# -46342_21-004_3_4.net
KiCad netlist of a schematic drawn in Altium Designer
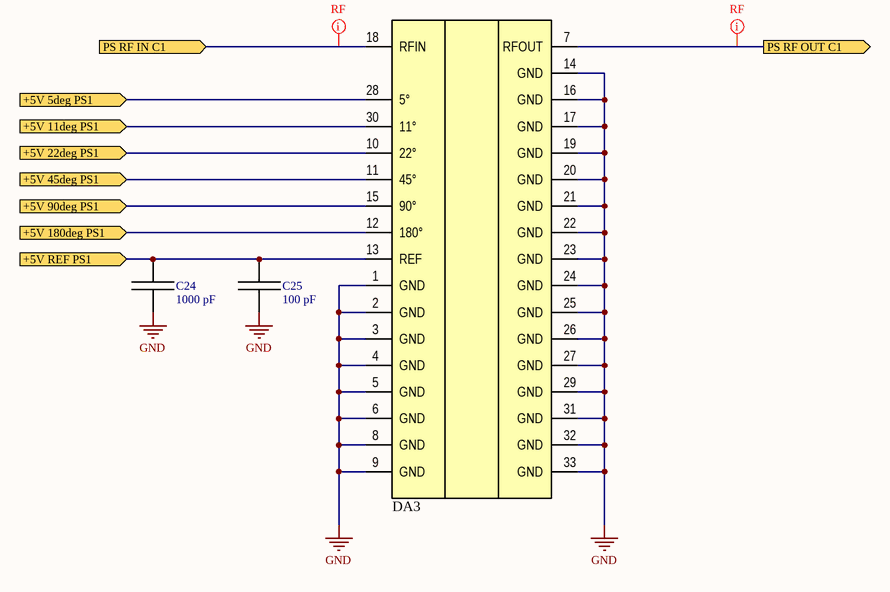
[diagram p0: МПСУ-46342.21-004 Э3 Лист4.SchDoc]

(export (version "E")
  (design (tool "Eeschema 10.0.6"))
  (components
    (comp (ref "C24")
      (value "1000 pF")
      (footprint "CAPC100X50X55L20N")
      (description "Capacitor, generic")
      (fields (field (name "TOLERANCE") "5 %"))
      (libsource (lib "StudentsLibrary") (part "Capacitor"))
    )
    (comp (ref "C25")
      (value "100 pF")
      (footprint "CAPC100X50X55L20N")
      (description "Capacitor, generic")
      (fields (field (name "TOLERANCE") "5 %"))
      (libsource (lib "StudentsLibrary") (part "Capacitor"))
    )
    (comp (ref "DA3")
      (value "TGP2105-SM")
      (footprint "QFN33P50_500X500X80L46X25T340N")
      (description "6 - 18 GHz 6-Bit Digital Phase Shifter (+Vc)")
      (fields (field (name "MANUFACTURER") "Qorvo"))
      (libsource (lib "receiver") (part "TGP2105-SM 1"))
    )
  )
  (nets
    (net (code "1") (name "/+5V 5deg PS1") (class "Default")
      (node (ref "DA3") (pin "28") (pinfunction "5°_28") (pintype "passive"))
    )
    (net (code "2") (name "/+5V 11deg PS1") (class "Default")
      (node (ref "DA3") (pin "30") (pinfunction "11°_30") (pintype "passive"))
    )
    (net (code "3") (name "/+5V 22deg PS1") (class "Default")
      (node (ref "DA3") (pin "10") (pinfunction "22°_10") (pintype "passive"))
    )
    (net (code "4") (name "/+5V 45deg PS1") (class "Default")
      (node (ref "DA3") (pin "11") (pinfunction "45°_11") (pintype "passive"))
    )
    (net (code "5") (name "/+5V 90deg PS1") (class "Default")
      (node (ref "DA3") (pin "15") (pinfunction "90°_15") (pintype "passive"))
    )
    (net (code "6") (name "/+5V 180deg PS1") (class "Default")
      (node (ref "DA3") (pin "12") (pinfunction "180°_12") (pintype "passive"))
    )
    (net (code "7") (name "/+5V REF PS1") (class "Default")
      (node (ref "C24") (pin "2") (pinfunction "2_2") (pintype "passive"))
      (node (ref "C25") (pin "2") (pinfunction "2_2") (pintype "passive"))
      (node (ref "DA3") (pin "13") (pinfunction "REF_13") (pintype "passive"))
    )
    (net (code "8") (name "/PS RF IN C1") (class "Default")
      (node (ref "DA3") (pin "18") (pinfunction "RFIN_18") (pintype "passive"))
    )
    (net (code "9") (name "/PS RF OUT C1") (class "Default")
      (node (ref "DA3") (pin "7") (pinfunction "RFOUT_7") (pintype "passive"))
    )
    (net (code "10") (name "GND") (class "Default")
      (node (ref "C24") (pin "1") (pinfunction "1_1") (pintype "passive"))
      (node (ref "C25") (pin "1") (pinfunction "1_1") (pintype "passive"))
      (node (ref "DA3") (pin "1") (pinfunction "GND_1") (pintype "passive"))
      (node (ref "DA3") (pin "14") (pinfunction "GND_14") (pintype "passive"))
      (node (ref "DA3") (pin "16") (pinfunction "GND_16") (pintype "passive"))
      (node (ref "DA3") (pin "17") (pinfunction "GND_17") (pintype "passive"))
      (node (ref "DA3") (pin "19") (pinfunction "GND_19") (pintype "passive"))
      (node (ref "DA3") (pin "2") (pinfunction "GND_2") (pintype "passive"))
      (node (ref "DA3") (pin "20") (pinfunction "GND_20") (pintype "passive"))
      (node (ref "DA3") (pin "21") (pinfunction "GND_21") (pintype "passive"))
      (node (ref "DA3") (pin "22") (pinfunction "GND_22") (pintype "passive"))
      (node (ref "DA3") (pin "23") (pinfunction "GND_23") (pintype "passive"))
      (node (ref "DA3") (pin "24") (pinfunction "GND_24") (pintype "passive"))
      (node (ref "DA3") (pin "25") (pinfunction "GND_25") (pintype "passive"))
      (node (ref "DA3") (pin "26") (pinfunction "GND_26") (pintype "passive"))
      (node (ref "DA3") (pin "27") (pinfunction "GND_27") (pintype "passive"))
      (node (ref "DA3") (pin "29") (pinfunction "GND_29") (pintype "passive"))
      (node (ref "DA3") (pin "3") (pinfunction "GND_3") (pintype "passive"))
      (node (ref "DA3") (pin "31") (pinfunction "GND_31") (pintype "passive"))
      (node (ref "DA3") (pin "32") (pinfunction "GND_32") (pintype "passive"))
      (node (ref "DA3") (pin "33") (pinfunction "GND_33") (pintype "passive"))
      (node (ref "DA3") (pin "4") (pinfunction "GND_4") (pintype "passive"))
      (node (ref "DA3") (pin "5") (pinfunction "GND_5") (pintype "passive"))
      (node (ref "DA3") (pin "6") (pinfunction "GND_6") (pintype "passive"))
      (node (ref "DA3") (pin "8") (pinfunction "GND_8") (pintype "passive"))
      (node (ref "DA3") (pin "9") (pinfunction "GND_9") (pintype "passive"))
    )
  )
)
